# 3_ADC.net
KiCad netlist of a schematic drawn in Altium Designer
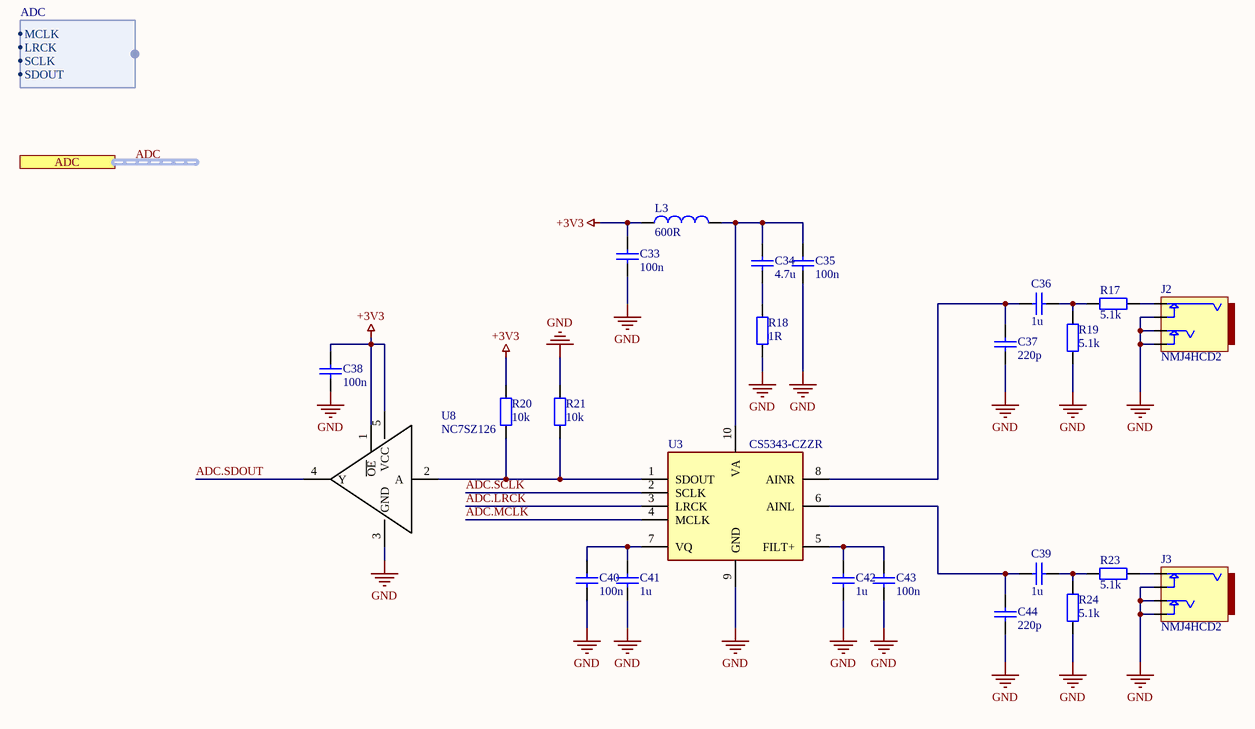
[diagram p0: [3] ADC.SchDoc]

(export (version "E")
  (design (tool "Eeschema 10.0.6"))
  (components
    (comp (ref "C33")
      (value "100n")
      (footprint "STguitar:Capacitor 0603")
      (description "Multilayer Ceramic Capacitors MLCC - SMD/SMT 0603 16VDC 0.1uF 10% X7R")
      (fields
        (field (name "MANUFACTURER PART NUMBER") "EMK107B7104KA-T")
        (field (name "MANUFACTURER") "Taiyo Yuden")
      )
      (libsource (lib "STguitar") (part "Capacitor 100n 10% 0603 EMK107B7104KA-T"))
    )
    (comp (ref "C34")
      (value "4.7u")
      (footprint "STguitar:Capacitor 0603")
      (description "Multilayer Ceramic Capacitors MLCC - SMD/SMT 0603 16VDC 4.7uF 10% X5R")
      (fields
        (field (name "MANUFACTURER PART NUMBER") "EMK107ABJ475KA-T")
        (field (name "MANUFACTURER") "Taiyo Yuden")
      )
      (libsource (lib "STguitar") (part "Capacitor 4.7u 10% 0603 EMK107ABJ475KA-T"))
    )
    (comp (ref "C35")
      (value "100n")
      (footprint "STguitar:Capacitor 0603")
      (description "Multilayer Ceramic Capacitors MLCC - SMD/SMT 0603 16VDC 0.1uF 10% X7R")
      (fields
        (field (name "MANUFACTURER PART NUMBER") "EMK107B7104KA-T")
        (field (name "MANUFACTURER") "Taiyo Yuden")
      )
      (libsource (lib "STguitar") (part "Capacitor 100n 10% 0603 EMK107B7104KA-T"))
    )
    (comp (ref "C36")
      (value "1u")
      (footprint "STguitar:Capacitor 0603")
      (description "Multilayer Ceramic Capacitors MLCC - SMD/SMT 0603 16VDC 1uF 10% X7R")
      (fields
        (field (name "MANUFACTURER PART NUMBER") "EMK107B7105KA-T")
        (field (name "MANUFACTURER") "Taiyo Yuden")
      )
      (libsource (lib "STguitar") (part "Capacitor 1u 10% 0603 EMK107B7105KA-T"))
    )
    (comp (ref "C37")
      (value "220p")
      (footprint "STguitar:Capacitor 0603")
      (description "Multilayer Ceramic Capacitors MLCC - SMD/SMT 0603 100VDC 220pF 20% NPO MID HIGH VOL")
      (fields
        (field (name "MANUFACTURER PART NUMBER") "HMK107SD221KA-T")
        (field (name "MANUFACTURER") "Taiyo Yuden")
      )
      (libsource (lib "STguitar") (part "Capacitor 220p 10% 0603 HMK107SD221KA-T"))
    )
    (comp (ref "C38")
      (value "100n")
      (footprint "STguitar:Capacitor 0603")
      (description "Multilayer Ceramic Capacitors MLCC - SMD/SMT 0603 16VDC 0.1uF 10% X7R")
      (fields
        (field (name "MANUFACTURER PART NUMBER") "EMK107B7104KA-T")
        (field (name "MANUFACTURER") "Taiyo Yuden")
      )
      (libsource (lib "STguitar") (part "Capacitor 100n 10% 0603 EMK107B7104KA-T"))
    )
    (comp (ref "C39")
      (value "1u")
      (footprint "STguitar:Capacitor 0603")
      (description "Multilayer Ceramic Capacitors MLCC - SMD/SMT 0603 16VDC 1uF 10% X7R")
      (fields
        (field (name "MANUFACTURER PART NUMBER") "EMK107B7105KA-T")
        (field (name "MANUFACTURER") "Taiyo Yuden")
      )
      (libsource (lib "STguitar") (part "Capacitor 1u 10% 0603 EMK107B7105KA-T"))
    )
    (comp (ref "C40")
      (value "100n")
      (footprint "STguitar:Capacitor 0603")
      (description "Multilayer Ceramic Capacitors MLCC - SMD/SMT 0603 16VDC 0.1uF 10% X7R")
      (fields
        (field (name "MANUFACTURER PART NUMBER") "EMK107B7104KA-T")
        (field (name "MANUFACTURER") "Taiyo Yuden")
      )
      (libsource (lib "STguitar") (part "Capacitor 100n 10% 0603 EMK107B7104KA-T"))
    )
    (comp (ref "C41")
      (value "1u")
      (footprint "STguitar:Capacitor 0603")
      (description "Multilayer Ceramic Capacitors MLCC - SMD/SMT 0603 16VDC 1uF 10% X7R")
      (fields
        (field (name "MANUFACTURER PART NUMBER") "EMK107B7105KA-T")
        (field (name "MANUFACTURER") "Taiyo Yuden")
      )
      (libsource (lib "STguitar") (part "Capacitor 1u 10% 0603 EMK107B7105KA-T"))
    )
    (comp (ref "C42")
      (value "1u")
      (footprint "STguitar:Capacitor 0603")
      (description "Multilayer Ceramic Capacitors MLCC - SMD/SMT 0603 16VDC 1uF 10% X7R")
      (fields
        (field (name "MANUFACTURER PART NUMBER") "EMK107B7105KA-T")
        (field (name "MANUFACTURER") "Taiyo Yuden")
      )
      (libsource (lib "STguitar") (part "Capacitor 1u 10% 0603 EMK107B7105KA-T"))
    )
    (comp (ref "C43")
      (value "100n")
      (footprint "STguitar:Capacitor 0603")
      (description "Multilayer Ceramic Capacitors MLCC - SMD/SMT 0603 16VDC 0.1uF 10% X7R")
      (fields
        (field (name "MANUFACTURER PART NUMBER") "EMK107B7104KA-T")
        (field (name "MANUFACTURER") "Taiyo Yuden")
      )
      (libsource (lib "STguitar") (part "Capacitor 100n 10% 0603 EMK107B7104KA-T"))
    )
    (comp (ref "C44")
      (value "220p")
      (footprint "STguitar:Capacitor 0603")
      (description "Multilayer Ceramic Capacitors MLCC - SMD/SMT 0603 100VDC 220pF 20% NPO MID HIGH VOL")
      (fields
        (field (name "MANUFACTURER PART NUMBER") "HMK107SD221KA-T")
        (field (name "MANUFACTURER") "Taiyo Yuden")
      )
      (libsource (lib "STguitar") (part "Capacitor 220p 10% 0603 HMK107SD221KA-T"))
    )
    (comp (ref "J2")
      (value "NMJ4HCD2")
      (footprint "STguitar:Mechanical NMJ4HCD2")
      (description "Phone Connectors 2C MONO 2-SPST NC")
      (fields (field (name "MANUFACTURER") "Neutrik"))
      (libsource (lib "STguitar") (part "Mechanical JACK Phone Connectors 2C MONO 2-SPST NC"))
    )
    (comp (ref "J3")
      (value "NMJ4HCD2")
      (footprint "STguitar:Mechanical NMJ4HCD2")
      (description "Phone Connectors 2C MONO 2-SPST NC")
      (fields (field (name "MANUFACTURER") "Neutrik"))
      (libsource (lib "STguitar") (part "Mechanical JACK Phone Connectors 2C MONO 2-SPST NC"))
    )
    (comp (ref "L3")
      (value "600R")
      (footprint "STguitar:Inductor 0603")
      (description "Ferrite Beads 600ohms 100MHz 300mA Monolithic 0603 SMD")
      (fields
        (field (name "MANUFACTURER PART NUMBER") "HZ0603C601R-10")
        (field (name "MANUFACTURER") "Laird Performance Materials")
      )
      (libsource (lib "STguitar") (part "Inductor 600R 1% 0603 HZ0603C601R-10"))
    )
    (comp (ref "R17")
      (value "5.1k")
      (footprint "STguitar:Resistor 0603")
      (description "Thin Film Resistors - SMD 1/10W 5.1K ohm 1% 50ppm")
      (fields
        (field (name "MANUFACTURER PART NUMBER") "RT0603FRE075K1L")
        (field (name "MANUFACTURER") "Yageo")
      )
      (libsource (lib "") (part "Resistor 5.1k 1% 0603 RT0603FRE075K1L_1"))
    )
    (comp (ref "R18")
      (value "1R")
      (footprint "STguitar:Resistor 0603")
      (description "Thin Film Resistors - SMD 1/10W 1 ohm ohm 50 ppm")
      (fields
        (field (name "MANUFACTURER PART NUMBER") "RT0603FRE071RL")
        (field (name "MANUFACTURER") "Yageo")
      )
      (libsource (lib "STguitar") (part "Resistor 1R 1% 0603 RT0603FRE071RL"))
    )
    (comp (ref "R19")
      (value "5.1k")
      (footprint "STguitar:Resistor 0603")
      (description "Thin Film Resistors - SMD 1/10W 5.1K ohm 1% 50ppm")
      (fields
        (field (name "MANUFACTURER PART NUMBER") "RT0603FRE075K1L")
        (field (name "MANUFACTURER") "Yageo")
      )
      (libsource (lib "STguitar") (part "Resistor 5.1k 1% 0603 RT0603FRE075K1L"))
    )
    (comp (ref "R20")
      (value "10k")
      (footprint "STguitar:Resistor 0603")
      (description "Thin Film Resistors - SMD 10K ohm 1% 1/10W")
      (fields
        (field (name "MANUFACTURER PART NUMBER") "RT0603FRE0710KL")
        (field (name "MANUFACTURER") "Yageo")
      )
      (libsource (lib "STguitar") (part "Resistor 10k 1% 0603 RT0603FRE0710KL"))
    )
    (comp (ref "R21")
      (value "10k")
      (footprint "STguitar:Resistor 0603")
      (description "Thin Film Resistors - SMD 10K ohm 1% 1/10W")
      (fields
        (field (name "MANUFACTURER PART NUMBER") "RT0603FRE0710KL")
        (field (name "MANUFACTURER") "Yageo")
      )
      (libsource (lib "STguitar") (part "Resistor 10k 1% 0603 RT0603FRE0710KL"))
    )
    (comp (ref "R23")
      (value "5.1k")
      (footprint "STguitar:Resistor 0603")
      (description "Thin Film Resistors - SMD 1/10W 5.1K ohm 1% 50ppm")
      (fields
        (field (name "MANUFACTURER PART NUMBER") "RT0603FRE075K1L")
        (field (name "MANUFACTURER") "Yageo")
      )
      (libsource (lib "") (part "Resistor 5.1k 1% 0603 RT0603FRE075K1L_1"))
    )
    (comp (ref "R24")
      (value "5.1k")
      (footprint "STguitar:Resistor 0603")
      (description "Thin Film Resistors - SMD 1/10W 5.1K ohm 1% 50ppm")
      (fields
        (field (name "MANUFACTURER PART NUMBER") "RT0603FRE075K1L")
        (field (name "MANUFACTURER") "Yageo")
      )
      (libsource (lib "STguitar") (part "Resistor 5.1k 1% 0603 RT0603FRE075K1L"))
    )
    (comp (ref "U3")
      (value "CS5343-CZZR")
      (footprint "STguitar:TSSOP10")
      (description "Audio A/D Converter ICs IC 98dB 24-bit 96kHz Stereo ADC")
      (fields (field (name "MANUFACTURER") "Cirrus Logic"))
      (libsource (lib "STguitar") (part "IC Audio A/D Converter ICs IC 98dB 24-bit 96kHz Stereo ADC CS5343-CZZR"))
    )
    (comp (ref "U8")
      (value "NC7SZ126")
      (footprint "STguitar:SC70-5")
      (description "Buffers & Line Drivers UHS Buffer")
      (fields (field (name "MANUFACTURER") "ON Semiconductor / Fairchild"))
      (libsource (lib "STguitar") (part "IC Buffers & Line Drivers UHS Buffer NC7SZ126P5X"))
    )
  )
  (nets
    (net (code "2") (name "+3V3") (class "Default")
      (node (ref "C33") (pin "2") (pinfunction "2_2") (pintype "passive"))
      (node (ref "C38") (pin "2") (pinfunction "2_2") (pintype "passive"))
      (node (ref "L3") (pin "1") (pinfunction "1_1") (pintype "passive"))
      (node (ref "R20") (pin "2") (pinfunction "2_2") (pintype "passive"))
      (node (ref "U8") (pin "1") (pinfunction "~{OE}_1") (pintype "passive"))
      (node (ref "U8") (pin "5") (pinfunction "VCC_5") (pintype "passive"))
    )
    (net (code "3") (name "/ADC.LRCK") (class "Default")
      (node (ref "U3") (pin "3") (pinfunction "LRCK_3") (pintype "passive"))
    )
    (net (code "4") (name "/ADC.MCLK") (class "Default")
      (node (ref "U3") (pin "4") (pinfunction "MCLK_4") (pintype "passive"))
    )
    (net (code "5") (name "/ADC.SCLK") (class "Default")
      (node (ref "U3") (pin "2") (pinfunction "SCLK_2") (pintype "passive"))
    )
    (net (code "6") (name "/ADC.SDOUT") (class "Default")
      (node (ref "U8") (pin "4") (pinfunction "Y_4") (pintype "passive"))
    )
    (net (code "8") (name "GND") (class "Default")
      (node (ref "C33") (pin "1") (pinfunction "1_1") (pintype "passive"))
      (node (ref "C35") (pin "1") (pinfunction "1_1") (pintype "passive"))
      (node (ref "C37") (pin "1") (pinfunction "1_1") (pintype "passive"))
      (node (ref "C38") (pin "1") (pinfunction "1_1") (pintype "passive"))
      (node (ref "C40") (pin "1") (pinfunction "1_1") (pintype "passive"))
      (node (ref "C41") (pin "1") (pinfunction "1_1") (pintype "passive"))
      (node (ref "C42") (pin "1") (pinfunction "1_1") (pintype "passive"))
      (node (ref "C43") (pin "1") (pinfunction "1_1") (pintype "passive"))
      (node (ref "C44") (pin "1") (pinfunction "1_1") (pintype "passive"))
      (node (ref "J2") (pin "1") (pinfunction "S_1") (pintype "passive"))
      (node (ref "J2") (pin "2") (pinfunction "SN_2") (pintype "passive"))
      (node (ref "J2") (pin "4") (pinfunction "TN_4") (pintype "passive"))
      (node (ref "J3") (pin "1") (pinfunction "S_1") (pintype "passive"))
      (node (ref "J3") (pin "2") (pinfunction "SN_2") (pintype "passive"))
      (node (ref "J3") (pin "4") (pinfunction "TN_4") (pintype "passive"))
      (node (ref "R18") (pin "1") (pinfunction "1_1") (pintype "passive"))
      (node (ref "R19") (pin "1") (pinfunction "1_1") (pintype "passive"))
      (node (ref "R21") (pin "2") (pinfunction "2_2") (pintype "passive"))
      (node (ref "R24") (pin "1") (pinfunction "1_1") (pintype "passive"))
      (node (ref "U3") (pin "9") (pinfunction "GND_9") (pintype "passive"))
      (node (ref "U8") (pin "3") (pinfunction "GND_3") (pintype "passive"))
    )
    (net (code "9") (name "Net-(C34-Pad1)") (class "Default")
      (node (ref "C34") (pin "1") (pinfunction "1_1") (pintype "passive"))
      (node (ref "R18") (pin "2") (pinfunction "2_2") (pintype "passive"))
    )
    (net (code "10") (name "Net-(C36-Pad2)") (class "Default")
      (node (ref "C36") (pin "2") (pinfunction "2_2") (pintype "passive"))
      (node (ref "R17") (pin "1") (pinfunction "1_1") (pintype "passive"))
      (node (ref "R19") (pin "2") (pinfunction "2_2") (pintype "passive"))
    )
    (net (code "11") (name "Net-(C39-Pad2)") (class "Default")
      (node (ref "C39") (pin "2") (pinfunction "2_2") (pintype "passive"))
      (node (ref "R23") (pin "1") (pinfunction "1_1") (pintype "passive"))
      (node (ref "R24") (pin "2") (pinfunction "2_2") (pintype "passive"))
    )
    (net (code "12") (name "Net-(J2-T)") (class "Default")
      (node (ref "J2") (pin "3") (pinfunction "T_3") (pintype "passive"))
      (node (ref "R17") (pin "2") (pinfunction "2_2") (pintype "passive"))
    )
    (net (code "13") (name "Net-(J3-T)") (class "Default")
      (node (ref "J3") (pin "3") (pinfunction "T_3") (pintype "passive"))
      (node (ref "R23") (pin "2") (pinfunction "2_2") (pintype "passive"))
    )
    (net (code "14") (name "Net-(U3-AINL)") (class "Default")
      (node (ref "C39") (pin "1") (pinfunction "1_1") (pintype "passive"))
      (node (ref "C44") (pin "2") (pinfunction "2_2") (pintype "passive"))
      (node (ref "U3") (pin "6") (pinfunction "AINL_6") (pintype "passive"))
    )
    (net (code "15") (name "Net-(U3-AINR)") (class "Default")
      (node (ref "C36") (pin "1") (pinfunction "1_1") (pintype "passive"))
      (node (ref "C37") (pin "2") (pinfunction "2_2") (pintype "passive"))
      (node (ref "U3") (pin "8") (pinfunction "AINR_8") (pintype "passive"))
    )
    (net (code "16") (name "Net-(U3-FILT+)") (class "Default")
      (node (ref "C42") (pin "2") (pinfunction "2_2") (pintype "passive"))
      (node (ref "C43") (pin "2") (pinfunction "2_2") (pintype "passive"))
      (node (ref "U3") (pin "5") (pinfunction "FILT+_5") (pintype "passive"))
    )
    (net (code "17") (name "Net-(U3-SDOUT)") (class "Default")
      (node (ref "R20") (pin "1") (pinfunction "1_1") (pintype "passive"))
      (node (ref "R21") (pin "1") (pinfunction "1_1") (pintype "passive"))
      (node (ref "U3") (pin "1") (pinfunction "SDOUT_1") (pintype "passive"))
      (node (ref "U8") (pin "2") (pinfunction "A_2") (pintype "passive"))
    )
    (net (code "18") (name "Net-(U3-VA)") (class "Default")
      (node (ref "C34") (pin "2") (pinfunction "2_2") (pintype "passive"))
      (node (ref "C35") (pin "2") (pinfunction "2_2") (pintype "passive"))
      (node (ref "L3") (pin "2") (pinfunction "2_2") (pintype "passive"))
      (node (ref "U3") (pin "10") (pinfunction "VA_10") (pintype "passive"))
    )
    (net (code "19") (name "Net-(U3-VQ)") (class "Default")
      (node (ref "C40") (pin "2") (pinfunction "2_2") (pintype "passive"))
      (node (ref "C41") (pin "2") (pinfunction "2_2") (pintype "passive"))
      (node (ref "U3") (pin "7") (pinfunction "VQ_7") (pintype "passive"))
    )
  )
)
